# 04-OUTPUT.net
KiCad netlist of a schematic drawn in Altium Designer
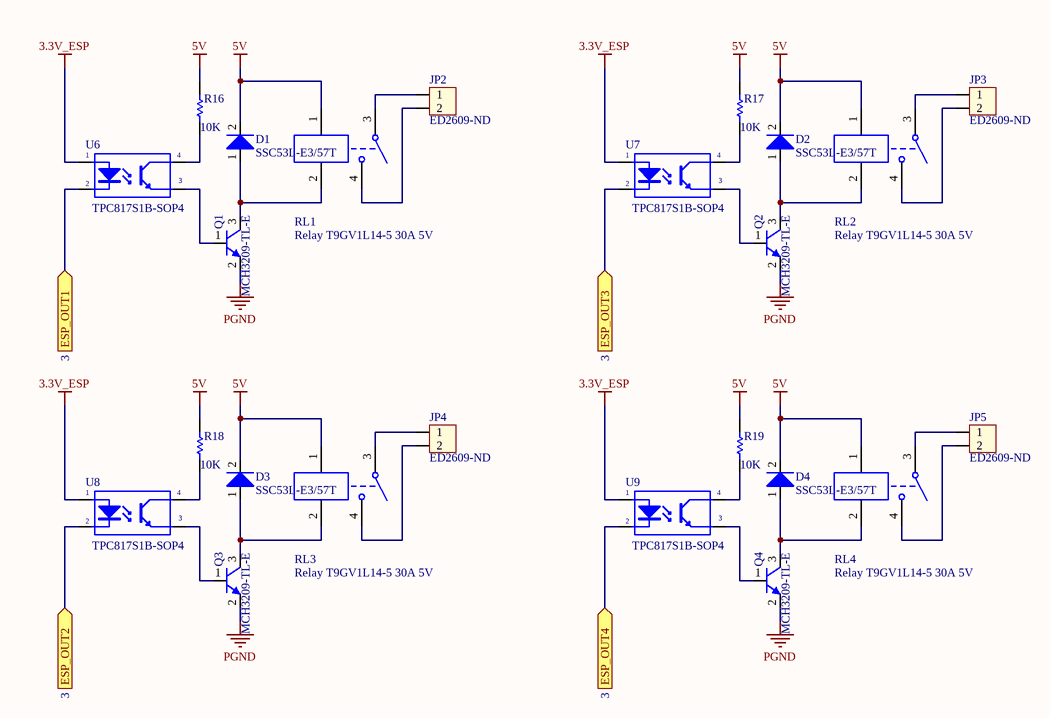
[diagram p0: 04-OUTPUT.SchDoc]

(export (version "E")
  (design (tool "Eeschema 10.0.6"))
  (components
    (comp (ref "D1")
      (value "SSC53L-E3/57T")
      (footprint "SSC53L-E3/57T")
      (description "DIODE SCHOTTKY 30V 5A DO214AB")
      (libsource (lib "lpson") (part "10A10"))
    )
    (comp (ref "D2")
      (value "SSC53L-E3/57T")
      (footprint "SSC53L-E3/57T")
      (description "DIODE SCHOTTKY 30V 5A DO214AB")
      (libsource (lib "lpson") (part "10A10"))
    )
    (comp (ref "D3")
      (value "SSC53L-E3/57T")
      (footprint "SSC53L-E3/57T")
      (description "DIODE SCHOTTKY 30V 5A DO214AB")
      (libsource (lib "lpson") (part "10A10"))
    )
    (comp (ref "D4")
      (value "SSC53L-E3/57T")
      (footprint "SSC53L-E3/57T")
      (description "DIODE SCHOTTKY 30V 5A DO214AB")
      (libsource (lib "lpson") (part "10A10"))
    )
    (comp (ref "JP2")
      (value "ED2609-ND")
      (footprint "DOMINO_OSTTC_2P")
      (description "2 Position Wire to Board Terminal Block Horizontal with Board 0.200\" (5.08mm) Through Hole")
      (libsource (lib "lpson") (part "Con2"))
    )
    (comp (ref "JP3")
      (value "ED2609-ND")
      (footprint "DOMINO_OSTTC_2P")
      (description "2 Position Wire to Board Terminal Block Horizontal with Board 0.200\" (5.08mm) Through Hole")
      (libsource (lib "lpson") (part "Con2"))
    )
    (comp (ref "JP4")
      (value "ED2609-ND")
      (footprint "DOMINO_OSTTC_2P")
      (description "2 Position Wire to Board Terminal Block Horizontal with Board 0.200\" (5.08mm) Through Hole")
      (libsource (lib "lpson") (part "Con2"))
    )
    (comp (ref "JP5")
      (value "ED2609-ND")
      (footprint "DOMINO_OSTTC_2P")
      (description "2 Position Wire to Board Terminal Block Horizontal with Board 0.200\" (5.08mm) Through Hole")
      (libsource (lib "lpson") (part "Con2"))
    )
    (comp (ref "Q1")
      (value "MCH3209-TL-E")
      (footprint "MCH3209-TL-E  SOT-323")
      (description "Bipolar (BJT) Transistor NPN 30V 3A 450MHz 800mW Surface Mount 3-MCPH")
      (libsource (lib "lpson") (part "2SC1815"))
    )
    (comp (ref "Q2")
      (value "MCH3209-TL-E")
      (footprint "MCH3209-TL-E  SOT-323")
      (description "Bipolar (BJT) Transistor NPN 30V 3A 450MHz 800mW Surface Mount 3-MCPH")
      (libsource (lib "lpson") (part "2SC1815"))
    )
    (comp (ref "Q3")
      (value "MCH3209-TL-E")
      (footprint "MCH3209-TL-E  SOT-323")
      (description "Bipolar (BJT) Transistor NPN 30V 3A 450MHz 800mW Surface Mount 3-MCPH")
      (libsource (lib "lpson") (part "2SC1815"))
    )
    (comp (ref "Q4")
      (value "MCH3209-TL-E")
      (footprint "MCH3209-TL-E  SOT-323")
      (description "Bipolar (BJT) Transistor NPN 30V 3A 450MHz 800mW Surface Mount 3-MCPH")
      (libsource (lib "lpson") (part "2SC1815"))
    )
    (comp (ref "R16")
      (value "10K")
      (footprint "Res 0805 SMD")
      (description "RES SMD 249K OHM 1% 1/10W 0805")
      (fields
        (field (name "MANUFACTURER") "Yageo")
        (field (name "MANUFACTURER PART NUMBER") "RC0603FR-07249KL")
      )
      (libsource (lib "GSHT_181013") (part "249K/R0805/1%"))
    )
    (comp (ref "R17")
      (value "10K")
      (footprint "Res 0805 SMD")
      (description "RES SMD 249K OHM 1% 1/10W 0805")
      (fields
        (field (name "MANUFACTURER") "Yageo")
        (field (name "MANUFACTURER PART NUMBER") "RC0603FR-07249KL")
      )
      (libsource (lib "GSHT_181013") (part "249K/R0805/1%"))
    )
    (comp (ref "R18")
      (value "10K")
      (footprint "Res 0805 SMD")
      (description "RES SMD 249K OHM 1% 1/10W 0805")
      (fields
        (field (name "MANUFACTURER") "Yageo")
        (field (name "MANUFACTURER PART NUMBER") "RC0603FR-07249KL")
      )
      (libsource (lib "GSHT_181013") (part "249K/R0805/1%"))
    )
    (comp (ref "R19")
      (value "10K")
      (footprint "Res 0805 SMD")
      (description "RES SMD 249K OHM 1% 1/10W 0805")
      (fields
        (field (name "MANUFACTURER") "Yageo")
        (field (name "MANUFACTURER PART NUMBER") "RC0603FR-07249KL")
      )
      (libsource (lib "GSHT_181013") (part "249K/R0805/1%"))
    )
    (comp (ref "RL1")
      (value "Relay T9GV1L14-5 30A 5V")
      (footprint "Relay T9GV1L14-5 30A 5V")
      (description "General Purpose Relay SPST-NO (1 Form A) 5VDC Coil Through Hole")
      (libsource (lib "PCB_ESP32_RFID") (part "Relay T9GV1L14-5 30A 5V"))
    )
    (comp (ref "RL2")
      (value "Relay T9GV1L14-5 30A 5V")
      (footprint "Relay T9GV1L14-5 30A 5V")
      (description "General Purpose Relay SPST-NO (1 Form A) 5VDC Coil Through Hole")
      (libsource (lib "PCB_ESP32_RFID") (part "Relay T9GV1L14-5 30A 5V"))
    )
    (comp (ref "RL3")
      (value "Relay T9GV1L14-5 30A 5V")
      (footprint "Relay T9GV1L14-5 30A 5V")
      (description "General Purpose Relay SPST-NO (1 Form A) 5VDC Coil Through Hole")
      (libsource (lib "PCB_ESP32_RFID") (part "Relay T9GV1L14-5 30A 5V"))
    )
    (comp (ref "RL4")
      (value "Relay T9GV1L14-5 30A 5V")
      (footprint "Relay T9GV1L14-5 30A 5V")
      (description "General Purpose Relay SPST-NO (1 Form A) 5VDC Coil Through Hole")
      (libsource (lib "PCB_ESP32_RFID") (part "Relay T9GV1L14-5 30A 5V"))
    )
    (comp (ref "U6")
      (value "TPC817S1B-SOP4")
      (footprint "TPC817-4SOP")
      (description "Optoisolator Transistor Output 5000Vrms 1 Channel 4-SOP")
      (libsource (lib "lpson") (part "PC817"))
    )
    (comp (ref "U7")
      (value "TPC817S1B-SOP4")
      (footprint "TPC817-4SOP")
      (description "Optoisolator Transistor Output 5000Vrms 1 Channel 4-SOP")
      (libsource (lib "lpson") (part "PC817"))
    )
    (comp (ref "U8")
      (value "TPC817S1B-SOP4")
      (footprint "TPC817-4SOP")
      (description "Optoisolator Transistor Output 5000Vrms 1 Channel 4-SOP")
      (libsource (lib "lpson") (part "PC817"))
    )
    (comp (ref "U9")
      (value "TPC817S1B-SOP4")
      (footprint "TPC817-4SOP")
      (description "Optoisolator Transistor Output 5000Vrms 1 Channel 4-SOP")
      (libsource (lib "lpson") (part "PC817"))
    )
  )
  (nets
    (net (code "1") (name "/ESP_OUT1") (class "Default")
      (node (ref "U6") (pin "2") (pinfunction "K_2") (pintype "passive"))
    )
    (net (code "2") (name "/ESP_OUT2") (class "Default")
      (node (ref "U8") (pin "2") (pinfunction "K_2") (pintype "passive"))
    )
    (net (code "3") (name "/ESP_OUT3") (class "Default")
      (node (ref "U7") (pin "2") (pinfunction "K_2") (pintype "passive"))
    )
    (net (code "4") (name "/ESP_OUT4") (class "Default")
      (node (ref "U9") (pin "2") (pinfunction "K_2") (pintype "passive"))
    )
    (net (code "5") (name "3.3V_ESP") (class "Default")
      (node (ref "U6") (pin "1") (pinfunction "A_1") (pintype "passive"))
      (node (ref "U7") (pin "1") (pinfunction "A_1") (pintype "passive"))
      (node (ref "U8") (pin "1") (pinfunction "A_1") (pintype "passive"))
      (node (ref "U9") (pin "1") (pinfunction "A_1") (pintype "passive"))
    )
    (net (code "6") (name "5V") (class "Default")
      (node (ref "D1") (pin "2") (pinfunction "K_2") (pintype "passive"))
      (node (ref "D2") (pin "2") (pinfunction "K_2") (pintype "passive"))
      (node (ref "D3") (pin "2") (pinfunction "K_2") (pintype "passive"))
      (node (ref "D4") (pin "2") (pinfunction "K_2") (pintype "passive"))
      (node (ref "R16") (pin "2") (pinfunction "2_2") (pintype "passive"))
      (node (ref "R17") (pin "2") (pinfunction "2_2") (pintype "passive"))
      (node (ref "R18") (pin "2") (pinfunction "2_2") (pintype "passive"))
      (node (ref "R19") (pin "2") (pinfunction "2_2") (pintype "passive"))
      (node (ref "RL1") (pin "1") (pinfunction "1_1") (pintype "passive"))
      (node (ref "RL2") (pin "1") (pinfunction "1_1") (pintype "passive"))
      (node (ref "RL3") (pin "1") (pinfunction "1_1") (pintype "passive"))
      (node (ref "RL4") (pin "1") (pinfunction "1_1") (pintype "passive"))
    )
    (net (code "7") (name "Net-(D1-A)") (class "Default")
      (node (ref "D1") (pin "1") (pinfunction "A_1") (pintype "passive"))
      (node (ref "Q1") (pin "3") (pinfunction "C_3") (pintype "passive"))
      (node (ref "RL1") (pin "2") (pinfunction "2_2") (pintype "passive"))
    )
    (net (code "8") (name "Net-(D2-A)") (class "Default")
      (node (ref "D2") (pin "1") (pinfunction "A_1") (pintype "passive"))
      (node (ref "Q2") (pin "3") (pinfunction "C_3") (pintype "passive"))
      (node (ref "RL2") (pin "2") (pinfunction "2_2") (pintype "passive"))
    )
    (net (code "9") (name "Net-(D3-A)") (class "Default")
      (node (ref "D3") (pin "1") (pinfunction "A_1") (pintype "passive"))
      (node (ref "Q3") (pin "3") (pinfunction "C_3") (pintype "passive"))
      (node (ref "RL3") (pin "2") (pinfunction "2_2") (pintype "passive"))
    )
    (net (code "10") (name "Net-(D4-A)") (class "Default")
      (node (ref "D4") (pin "1") (pinfunction "A_1") (pintype "passive"))
      (node (ref "Q4") (pin "3") (pinfunction "C_3") (pintype "passive"))
      (node (ref "RL4") (pin "2") (pinfunction "2_2") (pintype "passive"))
    )
    (net (code "11") (name "Net-(JP2-Pad1)") (class "Default")
      (node (ref "JP2") (pin "1") (pinfunction "1_1") (pintype "passive"))
      (node (ref "RL1") (pin "3") (pinfunction "3_3") (pintype "passive"))
    )
    (net (code "12") (name "Net-(JP2-Pad2)") (class "Default")
      (node (ref "JP2") (pin "2") (pinfunction "2_2") (pintype "passive"))
      (node (ref "RL1") (pin "4") (pinfunction "4_4") (pintype "passive"))
    )
    (net (code "13") (name "Net-(JP3-Pad1)") (class "Default")
      (node (ref "JP3") (pin "1") (pinfunction "1_1") (pintype "passive"))
      (node (ref "RL2") (pin "3") (pinfunction "3_3") (pintype "passive"))
    )
    (net (code "14") (name "Net-(JP3-Pad2)") (class "Default")
      (node (ref "JP3") (pin "2") (pinfunction "2_2") (pintype "passive"))
      (node (ref "RL2") (pin "4") (pinfunction "4_4") (pintype "passive"))
    )
    (net (code "15") (name "Net-(JP4-Pad1)") (class "Default")
      (node (ref "JP4") (pin "1") (pinfunction "1_1") (pintype "passive"))
      (node (ref "RL3") (pin "3") (pinfunction "3_3") (pintype "passive"))
    )
    (net (code "16") (name "Net-(JP4-Pad2)") (class "Default")
      (node (ref "JP4") (pin "2") (pinfunction "2_2") (pintype "passive"))
      (node (ref "RL3") (pin "4") (pinfunction "4_4") (pintype "passive"))
    )
    (net (code "17") (name "Net-(JP5-Pad1)") (class "Default")
      (node (ref "JP5") (pin "1") (pinfunction "1_1") (pintype "passive"))
      (node (ref "RL4") (pin "3") (pinfunction "3_3") (pintype "passive"))
    )
    (net (code "18") (name "Net-(JP5-Pad2)") (class "Default")
      (node (ref "JP5") (pin "2") (pinfunction "2_2") (pintype "passive"))
      (node (ref "RL4") (pin "4") (pinfunction "4_4") (pintype "passive"))
    )
    (net (code "19") (name "Net-(Q1-B)") (class "Default")
      (node (ref "Q1") (pin "1") (pinfunction "B_1") (pintype "passive"))
      (node (ref "U6") (pin "3") (pinfunction "E_3") (pintype "passive"))
    )
    (net (code "20") (name "Net-(Q2-B)") (class "Default")
      (node (ref "Q2") (pin "1") (pinfunction "B_1") (pintype "passive"))
      (node (ref "U7") (pin "3") (pinfunction "E_3") (pintype "passive"))
    )
    (net (code "21") (name "Net-(Q3-B)") (class "Default")
      (node (ref "Q3") (pin "1") (pinfunction "B_1") (pintype "passive"))
      (node (ref "U8") (pin "3") (pinfunction "E_3") (pintype "passive"))
    )
    (net (code "22") (name "Net-(Q4-B)") (class "Default")
      (node (ref "Q4") (pin "1") (pinfunction "B_1") (pintype "passive"))
      (node (ref "U9") (pin "3") (pinfunction "E_3") (pintype "passive"))
    )
    (net (code "23") (name "Net-(U6-C)") (class "Default")
      (node (ref "R16") (pin "1") (pinfunction "1_1") (pintype "passive"))
      (node (ref "U6") (pin "4") (pinfunction "C_4") (pintype "passive"))
    )
    (net (code "24") (name "Net-(U7-C)") (class "Default")
      (node (ref "R17") (pin "1") (pinfunction "1_1") (pintype "passive"))
      (node (ref "U7") (pin "4") (pinfunction "C_4") (pintype "passive"))
    )
    (net (code "25") (name "Net-(U8-C)") (class "Default")
      (node (ref "R18") (pin "1") (pinfunction "1_1") (pintype "passive"))
      (node (ref "U8") (pin "4") (pinfunction "C_4") (pintype "passive"))
    )
    (net (code "26") (name "Net-(U9-C)") (class "Default")
      (node (ref "R19") (pin "1") (pinfunction "1_1") (pintype "passive"))
      (node (ref "U9") (pin "4") (pinfunction "C_4") (pintype "passive"))
    )
    (net (code "27") (name "PGND") (class "Default")
      (node (ref "Q1") (pin "2") (pinfunction "E_2") (pintype "passive"))
      (node (ref "Q2") (pin "2") (pinfunction "E_2") (pintype "passive"))
      (node (ref "Q3") (pin "2") (pinfunction "E_2") (pintype "passive"))
      (node (ref "Q4") (pin "2") (pinfunction "E_2") (pintype "passive"))
    )
  )
)
